# ftdi_programmer_to_atmega_328p_blink.net
KiCad netlist of a schematic drawn in EAGLE
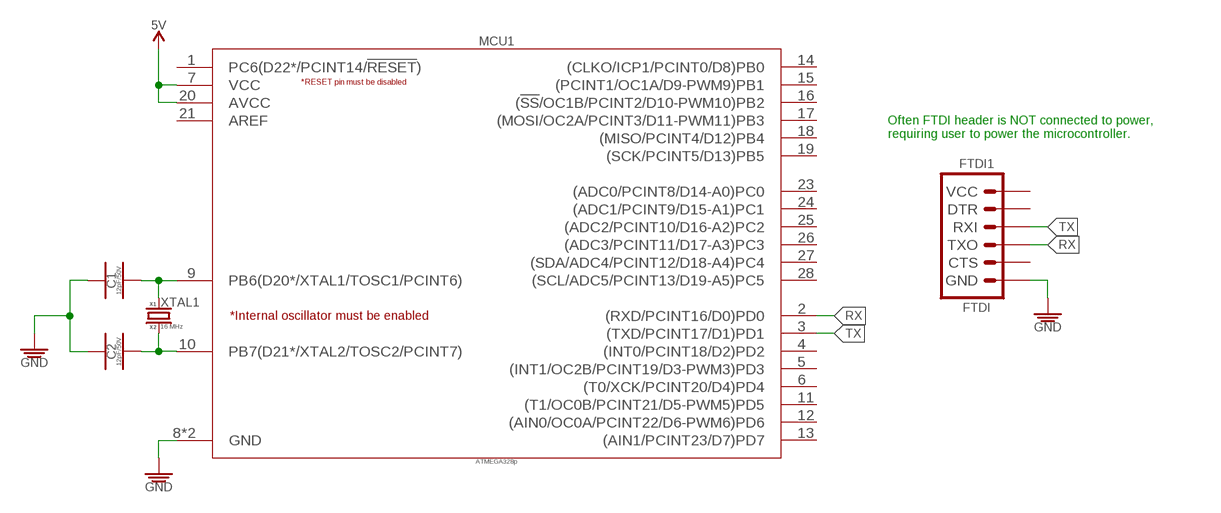
[diagram p0: schematic, sheet 1]

(export (version "E")
  (design (tool "Eeschema 10.0.6"))
  (components
    (comp (ref "C1")
      (value "12pF/50V")
      (footprint "eagle-import:_CER_PTH_LS2.5_L4-W2.5-H5.58")
      (fields (field (name "MFR") "Vishay BC Components") (field (name "MPN") "K120J15C0GF5TL2"))
      (libsource (lib "eagle-import") (part "12PF_PTH-CER_50V-5%"))
    )
    (comp (ref "C2")
      (value "12pF/50V")
      (footprint "eagle-import:_CER_PTH_LS2.5_L4-W2.5-H5.58")
      (fields (field (name "MFR") "Vishay BC Components") (field (name "MPN") "K120J15C0GF5TL2"))
      (libsource (lib "eagle-import") (part "12PF_PTH-CER_50V-5%"))
    )
    (comp (ref "FTDI1")
      (value "FTDI")
      (footprint "eagle-import:HDRV6W64P254_1X6_1524X254X838B_FTDI")
      (fields (field (name "MFR") "SparkFun Electronics") (field (name "MPN") "DEV-09873"))
      (libsource (lib "eagle-import") (part "FTDI_PTH_VERT_MALE_2.54MM"))
    )
    (comp (ref "MCU1")
      (value "ATMEGA328p")
      (footprint "eagle-import:DIP762W53P254L3467H472Q28B")
      (fields (field (name "MFR") "Microchip Technology") (field (name "MPN") "ATMEGA328P-PU"))
      (libsource (lib "eagle-import") (part "ATMEGA328P-28_28-PDIP_8BIT_32KB"))
    )
    (comp (ref "XTAL1")
      (value "16 MHz")
      (footprint "eagle-import:HC-49_US")
      (fields (field (name "MFR") "Abracon LLC") (field (name "MPN") "ABL-16.000MHZ-B2"))
      (libsource (lib "eagle-import") (part "CRYSTAL_ABL_16MHZ_18PF"))
    )
  )
  (nets
    (net (code "1") (name "5V") (class "Default")
      (node (ref "MCU1") (pin "20") (pinfunction "AVCC_20") (pintype "power_in"))
      (node (ref "MCU1") (pin "7") (pinfunction "VCC_7") (pintype "power_in"))
    )
    (net (code "2") (name "GND") (class "Default")
      (node (ref "C1") (pin "P$1") (pinfunction "1_P$1") (pintype "passive"))
      (node (ref "C2") (pin "P$1") (pinfunction "1_P$1") (pintype "passive"))
      (node (ref "FTDI1") (pin "GND") (pinfunction "GND_GND") (pintype "power_in"))
      (node (ref "MCU1") (pin "22") (pinfunction "GND_22") (pintype "power_in"))
      (node (ref "MCU1") (pin "8") (pinfunction "GND_8") (pintype "power_in"))
    )
    (net (code "3") (name "Net-(C1-2)") (class "Default")
      (node (ref "C1") (pin "P$2") (pinfunction "2_P$2") (pintype "passive"))
      (node (ref "MCU1") (pin "9") (pinfunction "PB6(D20*/XTAL1/TOSC1/PCINT6)_9") (pintype "bidirectional"))
      (node (ref "XTAL1") (pin "P$1") (pinfunction "XTAL1_P$1") (pintype "passive"))
    )
    (net (code "4") (name "Net-(C2-2)") (class "Default")
      (node (ref "C2") (pin "P$2") (pinfunction "2_P$2") (pintype "passive"))
      (node (ref "MCU1") (pin "10") (pinfunction "PB7(D21*/XTAL2/TOSC2/PCINT7)_10") (pintype "bidirectional"))
      (node (ref "XTAL1") (pin "P$2") (pinfunction "XTAL2_P$2") (pintype "passive"))
    )
    (net (code "5") (name "RX") (class "Default")
      (node (ref "FTDI1") (pin "TX") (pinfunction "TXO_TX") (pintype "output"))
      (node (ref "MCU1") (pin "2") (pinfunction "(RXD/PCINT16/D0)PD0_2") (pintype "bidirectional"))
    )
    (net (code "6") (name "TX") (class "Default")
      (node (ref "FTDI1") (pin "RX") (pinfunction "RXI_RX") (pintype "input"))
      (node (ref "MCU1") (pin "3") (pinfunction "(TXD/PCINT17/D1)PD1_3") (pintype "bidirectional"))
    )
    (net (code "7") (name "unconnected-(FTDI1-PadCTS)") (class "Default")
      (node (ref "FTDI1") (pin "CTS") (pinfunction "CTS_CTS") (pintype "bidirectional"))
    )
    (net (code "8") (name "unconnected-(FTDI1-PadDTR)") (class "Default")
      (node (ref "FTDI1") (pin "DTR") (pinfunction "DTR_DTR") (pintype "bidirectional"))
    )
    (net (code "9") (name "unconnected-(FTDI1-PadVCC)") (class "Default")
      (node (ref "FTDI1") (pin "VCC") (pinfunction "VCC_VCC") (pintype "no_connect"))
    )
    (net (code "10") (name "unconnected-(MCU1-(ADC0{slash}PCINT8{slash}D14-A0)PC0-Pad23)") (class "Default")
      (node (ref "MCU1") (pin "23") (pinfunction "(ADC0/PCINT8/D14-A0)PC0_23") (pintype "bidirectional"))
    )
    (net (code "11") (name "unconnected-(MCU1-(ADC1{slash}PCINT9{slash}D15-A1)PC1-Pad24)") (class "Default")
      (node (ref "MCU1") (pin "24") (pinfunction "(ADC1/PCINT9/D15-A1)PC1_24") (pintype "bidirectional"))
    )
    (net (code "12") (name "unconnected-(MCU1-(ADC2{slash}PCINT10{slash}D16-A2)PC2-Pad25)") (class "Default")
      (node (ref "MCU1") (pin "25") (pinfunction "(ADC2/PCINT10/D16-A2)PC2_25") (pintype "bidirectional"))
    )
    (net (code "13") (name "unconnected-(MCU1-(ADC3{slash}PCINT11{slash}D17-A3)PC3-Pad26)") (class "Default")
      (node (ref "MCU1") (pin "26") (pinfunction "(ADC3/PCINT11/D17-A3)PC3_26") (pintype "bidirectional"))
    )
    (net (code "14") (name "unconnected-(MCU1-(AIN0{slash}OC0A{slash}PCINT22{slash}D6-PWM6)PD6-Pad12)") (class "Default")
      (node (ref "MCU1") (pin "12") (pinfunction "(AIN0/OC0A/PCINT22/D6-PWM6)PD6_12") (pintype "bidirectional"))
    )
    (net (code "15") (name "unconnected-(MCU1-(AIN1{slash}PCINT23{slash}D7)PD7-Pad13)") (class "Default")
      (node (ref "MCU1") (pin "13") (pinfunction "(AIN1/PCINT23/D7)PD7_13") (pintype "bidirectional"))
    )
    (net (code "16") (name "unconnected-(MCU1-(CLKO{slash}ICP1{slash}PCINT0{slash}D8)PB0-Pad14)") (class "Default")
      (node (ref "MCU1") (pin "14") (pinfunction "(CLKO/ICP1/PCINT0/D8)PB0_14") (pintype "bidirectional"))
    )
    (net (code "17") (name "unconnected-(MCU1-(INT0{slash}PCINT18{slash}D2)PD2-Pad4)") (class "Default")
      (node (ref "MCU1") (pin "4") (pinfunction "(INT0/PCINT18/D2)PD2_4") (pintype "bidirectional"))
    )
    (net (code "18") (name "unconnected-(MCU1-(INT1{slash}OC2B{slash}PCINT19{slash}D3-PWM3)PD3-Pad5)") (class "Default")
      (node (ref "MCU1") (pin "5") (pinfunction "(INT1/OC2B/PCINT19/D3-PWM3)PD3_5") (pintype "bidirectional"))
    )
    (net (code "19") (name "unconnected-(MCU1-(MISO{slash}PCINT4{slash}D12)PB4-Pad18)") (class "Default")
      (node (ref "MCU1") (pin "18") (pinfunction "(MISO/PCINT4/D12)PB4_18") (pintype "bidirectional"))
    )
    (net (code "20") (name "unconnected-(MCU1-(MOSI{slash}OC2A{slash}PCINT3{slash}D11-PWM11)PB3-Pad17)") (class "Default")
      (node (ref "MCU1") (pin "17") (pinfunction "(MOSI/OC2A/PCINT3/D11-PWM11)PB3_17") (pintype "bidirectional"))
    )
    (net (code "21") (name "unconnected-(MCU1-(PCINT1{slash}OC1A{slash}D9-PWM9)PB1-Pad15)") (class "Default")
      (node (ref "MCU1") (pin "15") (pinfunction "(PCINT1/OC1A/D9-PWM9)PB1_15") (pintype "bidirectional"))
    )
    (net (code "22") (name "unconnected-(MCU1-(SCK{slash}PCINT5{slash}D13)PB5-Pad19)") (class "Default")
      (node (ref "MCU1") (pin "19") (pinfunction "(SCK/PCINT5/D13)PB5_19") (pintype "bidirectional"))
    )
    (net (code "23") (name "unconnected-(MCU1-(SCL{slash}ADC5{slash}PCINT13{slash}D19-A5)PC5-Pad28)") (class "Default")
      (node (ref "MCU1") (pin "28") (pinfunction "(SCL/ADC5/PCINT13/D19-A5)PC5_28") (pintype "bidirectional"))
    )
    (net (code "24") (name "unconnected-(MCU1-(SDA{slash}ADC4{slash}PCINT12{slash}D18-A4)PC4-Pad27)") (class "Default")
      (node (ref "MCU1") (pin "27") (pinfunction "(SDA/ADC4/PCINT12/D18-A4)PC4_27") (pintype "bidirectional"))
    )
    (net (code "25") (name "unconnected-(MCU1-(T0{slash}XCK{slash}PCINT20{slash}D4)PD4-Pad6)") (class "Default")
      (node (ref "MCU1") (pin "6") (pinfunction "(T0/XCK/PCINT20/D4)PD4_6") (pintype "bidirectional"))
    )
    (net (code "26") (name "unconnected-(MCU1-(T1{slash}OC0B{slash}PCINT21{slash}D5-PWM5)PD5-Pad11)") (class "Default")
      (node (ref "MCU1") (pin "11") (pinfunction "(T1/OC0B/PCINT21/D5-PWM5)PD5_11") (pintype "bidirectional"))
    )
    (net (code "27") (name "unconnected-(MCU1-(~{SS}{slash}OC1B{slash}PCINT2{slash}D10-PWM10)PB2-Pad16)") (class "Default")
      (node (ref "MCU1") (pin "16") (pinfunction "(~{SS}/OC1B/PCINT2/D10-PWM10)PB2_16") (pintype "bidirectional"))
    )
    (net (code "28") (name "unconnected-(MCU1-AREF-Pad21)") (class "Default")
      (node (ref "MCU1") (pin "21") (pinfunction "AREF_21") (pintype "passive"))
    )
    (net (code "29") (name "unconnected-(MCU1-PC6(D22*{slash}PCINT14{slash}~{RESET})-Pad1)") (class "Default")
      (node (ref "MCU1") (pin "1") (pinfunction "PC6(D22*/PCINT14/~{RESET})_1") (pintype "bidirectional"))
    )
  )
)
